# HelloWorld_Drill.net
KiCad netlist of a schematic drawn in EAGLE
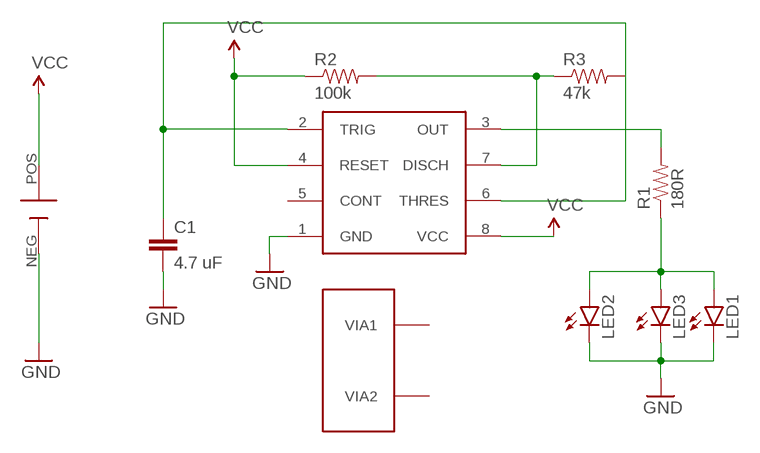
[diagram p0: schematic, sheet 1]

(export (version "E")
  (design (tool "Eeschema 10.0.6"))
  (components
    (comp (ref "C1")
      (value "4.7 uF")
      (footprint "eagle-import:C1206")
      (libsource (lib "eagle-import") (part "C-EUC1206"))
    )
    (comp (ref "LED1")
      (value "LED1206")
      (footprint "eagle-import:LED-1206")
      (libsource (lib "eagle-import") (part "LED1206"))
    )
    (comp (ref "LED2")
      (value "LED1206")
      (footprint "eagle-import:LED-1206")
      (libsource (lib "eagle-import") (part "LED1206"))
    )
    (comp (ref "LED3")
      (value "LED1206")
      (footprint "eagle-import:LED-1206")
      (libsource (lib "eagle-import") (part "LED1206"))
    )
    (comp (ref "R1")
      (value "180R")
      (footprint "eagle-import:1206")
      (libsource (lib "eagle-import") (part "RESISTOR1206"))
    )
    (comp (ref "R2")
      (value "100k")
      (footprint "eagle-import:1206")
      (libsource (lib "eagle-import") (part "RESISTOR1206"))
    )
    (comp (ref "R3")
      (value "47k")
      (footprint "eagle-import:1206")
      (libsource (lib "eagle-import") (part "RESISTOR1206"))
    )
    (comp (ref "U$1")
      (value "SMD_BATTERY_9V")
      (footprint "eagle-import:SMD_BATTERY_PADS")
      (libsource (lib "eagle-import") (part "SMD_BATTERY_9V"))
    )
    (comp (ref "U$2")
      (value "2X3_BOARD")
      (footprint "eagle-import:2X3_BOARD")
      (libsource (lib "eagle-import") (part "2X3_BOARD"))
    )
    (comp (ref "U1")
      (value "NE555PSR")
      (footprint "eagle-import:PS_R-PDSO-G8")
      (libsource (lib "eagle-import") (part "NE555PSR"))
    )
  )
  (nets
    (net (code "1") (name "GND") (class "Default")
      (node (ref "C1") (pin "2") (pinfunction "2_2") (pintype "passive"))
      (node (ref "LED1") (pin "C") (pinfunction "C_C") (pintype "passive"))
      (node (ref "LED2") (pin "C") (pinfunction "C_C") (pintype "passive"))
      (node (ref "LED3") (pin "C") (pinfunction "C_C") (pintype "passive"))
      (node (ref "U$1") (pin "NEG") (pinfunction "NEG_NEG") (pintype "bidirectional"))
      (node (ref "U1") (pin "1") (pinfunction "GND_1") (pintype "bidirectional"))
    )
    (net (code "2") (name "Net-(LED1-PadA)") (class "Default")
      (node (ref "LED1") (pin "A") (pinfunction "A_A") (pintype "passive"))
      (node (ref "LED2") (pin "A") (pinfunction "A_A") (pintype "passive"))
      (node (ref "LED3") (pin "A") (pinfunction "A_A") (pintype "passive"))
      (node (ref "R1") (pin "1") (pinfunction "1_1") (pintype "passive"))
    )
    (net (code "3") (name "Net-(U1-DISCH)") (class "Default")
      (node (ref "R2") (pin "2") (pinfunction "2_2") (pintype "passive"))
      (node (ref "R3") (pin "1") (pinfunction "1_1") (pintype "passive"))
      (node (ref "U1") (pin "7") (pinfunction "DISCH_7") (pintype "bidirectional"))
    )
    (net (code "4") (name "Net-(U1-OUT)") (class "Default")
      (node (ref "R1") (pin "2") (pinfunction "2_2") (pintype "passive"))
      (node (ref "U1") (pin "3") (pinfunction "OUT_3") (pintype "bidirectional"))
    )
    (net (code "5") (name "Net-(U1-THRES)") (class "Default")
      (node (ref "C1") (pin "1") (pinfunction "1_1") (pintype "passive"))
      (node (ref "R3") (pin "2") (pinfunction "2_2") (pintype "passive"))
      (node (ref "U1") (pin "2") (pinfunction "TRIG_2") (pintype "bidirectional"))
      (node (ref "U1") (pin "6") (pinfunction "THRES_6") (pintype "bidirectional"))
    )
    (net (code "6") (name "VCC") (class "Default")
      (node (ref "R2") (pin "1") (pinfunction "1_1") (pintype "passive"))
      (node (ref "U$1") (pin "POS") (pinfunction "POS_POS") (pintype "bidirectional"))
      (node (ref "U1") (pin "4") (pinfunction "RESET_4") (pintype "bidirectional"))
      (node (ref "U1") (pin "8") (pinfunction "VCC_8") (pintype "bidirectional"))
    )
    (net (code "7") (name "unconnected-(U$2-VIA1-PadP$1)") (class "Default")
      (node (ref "U$2") (pin "P$1") (pinfunction "VIA1_P$1") (pintype "bidirectional"))
    )
    (net (code "8") (name "unconnected-(U$2-VIA2-PadP$2)") (class "Default")
      (node (ref "U$2") (pin "P$2") (pinfunction "VIA2_P$2") (pintype "bidirectional"))
    )
    (net (code "9") (name "unconnected-(U1-CONT-Pad5)") (class "Default")
      (node (ref "U1") (pin "5") (pinfunction "CONT_5") (pintype "bidirectional"))
    )
  )
)
